# bms_2.net
KiCad netlist of a schematic drawn in EAGLE
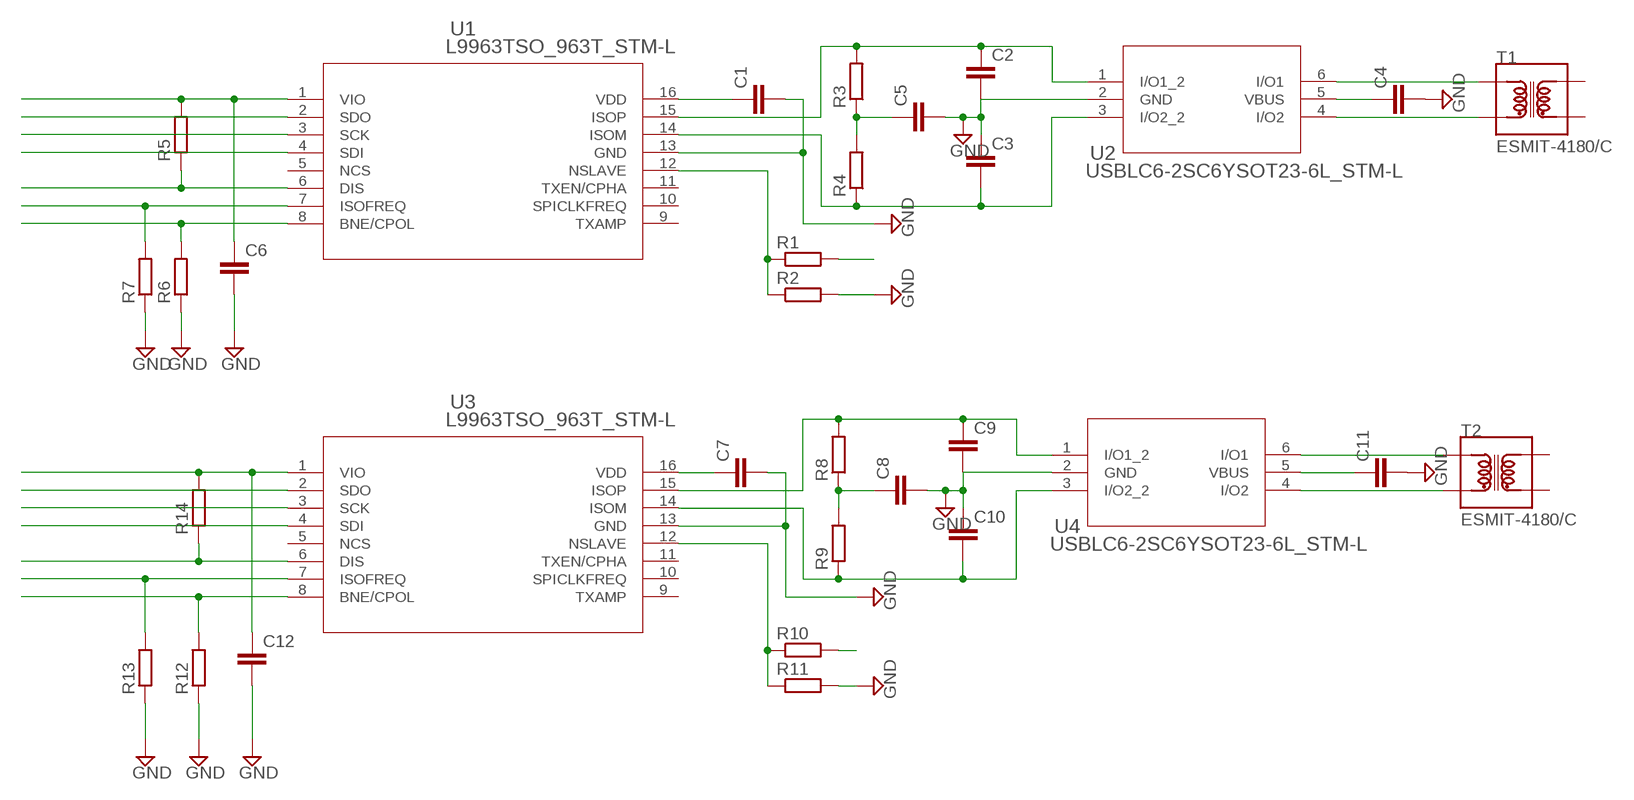
[diagram p0: schematic, sheet 1]

(export (version "E")
  (design (tool "Eeschema 10.0.6"))
  (components
    (comp (ref "C1")
      (value "C-EUC0402")
      (footprint "eagle-import:C0402")
      (libsource (lib "eagle-import") (part "C-EUC0402"))
    )
    (comp (ref "C2")
      (value "C-EUC0402")
      (footprint "eagle-import:C0402")
      (libsource (lib "eagle-import") (part "C-EUC0402"))
    )
    (comp (ref "C3")
      (value "C-EUC0402")
      (footprint "eagle-import:C0402")
      (libsource (lib "eagle-import") (part "C-EUC0402"))
    )
    (comp (ref "C4")
      (value "C-EUC0402")
      (footprint "eagle-import:C0402")
      (libsource (lib "eagle-import") (part "C-EUC0402"))
    )
    (comp (ref "C5")
      (value "C-EUC0402")
      (footprint "eagle-import:C0402")
      (libsource (lib "eagle-import") (part "C-EUC0402"))
    )
    (comp (ref "C6")
      (value "C-EUC0402")
      (footprint "eagle-import:C0402")
      (libsource (lib "eagle-import") (part "C-EUC0402"))
    )
    (comp (ref "C7")
      (value "C-EUC0402")
      (footprint "eagle-import:C0402")
      (libsource (lib "eagle-import") (part "C-EUC0402"))
    )
    (comp (ref "C8")
      (value "C-EUC0402")
      (footprint "eagle-import:C0402")
      (libsource (lib "eagle-import") (part "C-EUC0402"))
    )
    (comp (ref "C9")
      (value "C-EUC0402")
      (footprint "eagle-import:C0402")
      (libsource (lib "eagle-import") (part "C-EUC0402"))
    )
    (comp (ref "C10")
      (value "C-EUC0402")
      (footprint "eagle-import:C0402")
      (libsource (lib "eagle-import") (part "C-EUC0402"))
    )
    (comp (ref "C11")
      (value "C-EUC0402")
      (footprint "eagle-import:C0402")
      (libsource (lib "eagle-import") (part "C-EUC0402"))
    )
    (comp (ref "C12")
      (value "C-EUC0402")
      (footprint "eagle-import:C0402")
      (libsource (lib "eagle-import") (part "C-EUC0402"))
    )
    (comp (ref "R1")
      (value "R-EU_M0805")
      (footprint "eagle-import:M0805")
      (libsource (lib "eagle-import") (part "R-EU_M0805"))
    )
    (comp (ref "R2")
      (value "R-EU_M0805")
      (footprint "eagle-import:M0805")
      (libsource (lib "eagle-import") (part "R-EU_M0805"))
    )
    (comp (ref "R3")
      (value "R-EU_M0805")
      (footprint "eagle-import:M0805")
      (libsource (lib "eagle-import") (part "R-EU_M0805"))
    )
    (comp (ref "R4")
      (value "R-EU_M0805")
      (footprint "eagle-import:M0805")
      (libsource (lib "eagle-import") (part "R-EU_M0805"))
    )
    (comp (ref "R5")
      (value "R-EU_M0805")
      (footprint "eagle-import:M0805")
      (libsource (lib "eagle-import") (part "R-EU_M0805"))
    )
    (comp (ref "R6")
      (value "R-EU_M0805")
      (footprint "eagle-import:M0805")
      (libsource (lib "eagle-import") (part "R-EU_M0805"))
    )
    (comp (ref "R7")
      (value "R-EU_M0805")
      (footprint "eagle-import:M0805")
      (libsource (lib "eagle-import") (part "R-EU_M0805"))
    )
    (comp (ref "R8")
      (value "R-EU_M0805")
      (footprint "eagle-import:M0805")
      (libsource (lib "eagle-import") (part "R-EU_M0805"))
    )
    (comp (ref "R9")
      (value "R-EU_M0805")
      (footprint "eagle-import:M0805")
      (libsource (lib "eagle-import") (part "R-EU_M0805"))
    )
    (comp (ref "R10")
      (value "R-EU_M0805")
      (footprint "eagle-import:M0805")
      (libsource (lib "eagle-import") (part "R-EU_M0805"))
    )
    (comp (ref "R11")
      (value "R-EU_M0805")
      (footprint "eagle-import:M0805")
      (libsource (lib "eagle-import") (part "R-EU_M0805"))
    )
    (comp (ref "R12")
      (value "R-EU_M0805")
      (footprint "eagle-import:M0805")
      (libsource (lib "eagle-import") (part "R-EU_M0805"))
    )
    (comp (ref "R13")
      (value "R-EU_M0805")
      (footprint "eagle-import:M0805")
      (libsource (lib "eagle-import") (part "R-EU_M0805"))
    )
    (comp (ref "R14")
      (value "R-EU_M0805")
      (footprint "eagle-import:M0805")
      (libsource (lib "eagle-import") (part "R-EU_M0805"))
    )
    (comp (ref "T1")
      (value "ESMIT-4180/C")
      (footprint "eagle-import:XFMR_ESMIT-4180_C")
      (fields (field (name "MF") "Sumida America"))
      (libsource (lib "eagle-import") (part "ESMIT-4180/C"))
    )
    (comp (ref "T2")
      (value "ESMIT-4180/C")
      (footprint "eagle-import:XFMR_ESMIT-4180_C")
      (fields (field (name "MF") "Sumida America"))
      (libsource (lib "eagle-import") (part "ESMIT-4180/C"))
    )
    (comp (ref "U1")
      (value "L9963TSO_963T_STM-L")
      (footprint "eagle-import:SO_963T_STM-L")
      (fields
        (field (name "MANUFACTURER_PART_NUMBER") "L9963T")
        (field (name "COPYRIGHT") "Copyright (C) 2021 Ultra Librarian. All rights reserved.")
      )
      (libsource (lib "eagle-import") (part "L9963TSO_963T_STM-L"))
    )
    (comp (ref "U2")
      (value "USBLC6-2SC6YSOT23-6L_STM-L")
      (footprint "eagle-import:SOT23-6L_STM-L")
      (fields
        (field (name "MANUFACTURER_PART_NUMBER") "USBLC6-2SC6Y")
        (field (name "COPYRIGHT") "Copyright (C) 2021 Ultra Librarian. All rights reserved.")
      )
      (libsource (lib "eagle-import") (part "USBLC6-2SC6YSOT23-6L_STM-L"))
    )
    (comp (ref "U3")
      (value "L9963TSO_963T_STM-L")
      (footprint "eagle-import:SO_963T_STM-L")
      (fields
        (field (name "MANUFACTURER_PART_NUMBER") "L9963T")
        (field (name "COPYRIGHT") "Copyright (C) 2021 Ultra Librarian. All rights reserved.")
      )
      (libsource (lib "eagle-import") (part "L9963TSO_963T_STM-L"))
    )
    (comp (ref "U4")
      (value "USBLC6-2SC6YSOT23-6L_STM-L")
      (footprint "eagle-import:SOT23-6L_STM-L")
      (fields
        (field (name "MANUFACTURER_PART_NUMBER") "USBLC6-2SC6Y")
        (field (name "COPYRIGHT") "Copyright (C) 2021 Ultra Librarian. All rights reserved.")
      )
      (libsource (lib "eagle-import") (part "USBLC6-2SC6YSOT23-6L_STM-L"))
    )
  )
  (nets
    (net (code "1") (name "GND") (class "Default")
      (node (ref "C1") (pin "2") (pinfunction "2_2") (pintype "passive"))
      (node (ref "C10") (pin "1") (pinfunction "1_1") (pintype "passive"))
      (node (ref "C11") (pin "2") (pinfunction "2_2") (pintype "passive"))
      (node (ref "C12") (pin "2") (pinfunction "2_2") (pintype "passive"))
      (node (ref "C2") (pin "2") (pinfunction "2_2") (pintype "passive"))
      (node (ref "C3") (pin "1") (pinfunction "1_1") (pintype "passive"))
      (node (ref "C4") (pin "2") (pinfunction "2_2") (pintype "passive"))
      (node (ref "C5") (pin "2") (pinfunction "2_2") (pintype "passive"))
      (node (ref "C6") (pin "2") (pinfunction "2_2") (pintype "passive"))
      (node (ref "C7") (pin "2") (pinfunction "2_2") (pintype "passive"))
      (node (ref "C8") (pin "2") (pinfunction "2_2") (pintype "passive"))
      (node (ref "C9") (pin "2") (pinfunction "2_2") (pintype "passive"))
      (node (ref "R11") (pin "2") (pinfunction "2_2") (pintype "passive"))
      (node (ref "R12") (pin "1") (pinfunction "1_1") (pintype "passive"))
      (node (ref "R13") (pin "1") (pinfunction "1_1") (pintype "passive"))
      (node (ref "R2") (pin "2") (pinfunction "2_2") (pintype "passive"))
      (node (ref "R6") (pin "1") (pinfunction "1_1") (pintype "passive"))
      (node (ref "R7") (pin "1") (pinfunction "1_1") (pintype "passive"))
      (node (ref "U1") (pin "13") (pinfunction "GND_13") (pintype "passive"))
      (node (ref "U2") (pin "2") (pinfunction "GND_2") (pintype "power_in"))
      (node (ref "U3") (pin "13") (pinfunction "GND_13") (pintype "passive"))
      (node (ref "U4") (pin "2") (pinfunction "GND_2") (pintype "power_in"))
    )
    (net (code "2") (name "Net-(C5-Pad1)") (class "Default")
      (node (ref "C5") (pin "1") (pinfunction "1_1") (pintype "passive"))
      (node (ref "R3") (pin "1") (pinfunction "1_1") (pintype "passive"))
      (node (ref "R4") (pin "2") (pinfunction "2_2") (pintype "passive"))
    )
    (net (code "3") (name "Net-(C8-Pad1)") (class "Default")
      (node (ref "C8") (pin "1") (pinfunction "1_1") (pintype "passive"))
      (node (ref "R8") (pin "1") (pinfunction "1_1") (pintype "passive"))
      (node (ref "R9") (pin "2") (pinfunction "2_2") (pintype "passive"))
    )
    (net (code "4") (name "Net-(U1-BNE{slash}CPOL)") (class "Default")
      (node (ref "R6") (pin "2") (pinfunction "2_2") (pintype "passive"))
      (node (ref "U1") (pin "8") (pinfunction "BNE/CPOL_8") (pintype "passive"))
    )
    (net (code "5") (name "Net-(U1-DIS)") (class "Default")
      (node (ref "R5") (pin "1") (pinfunction "1_1") (pintype "passive"))
      (node (ref "U1") (pin "6") (pinfunction "DIS_6") (pintype "passive"))
    )
    (net (code "6") (name "Net-(U1-ISOFREQ)") (class "Default")
      (node (ref "R7") (pin "2") (pinfunction "2_2") (pintype "passive"))
      (node (ref "U1") (pin "7") (pinfunction "ISOFREQ_7") (pintype "passive"))
    )
    (net (code "7") (name "Net-(U1-ISOM)") (class "Default")
      (node (ref "C3") (pin "2") (pinfunction "2_2") (pintype "passive"))
      (node (ref "R4") (pin "1") (pinfunction "1_1") (pintype "passive"))
      (node (ref "U1") (pin "14") (pinfunction "ISOM_14") (pintype "passive"))
      (node (ref "U2") (pin "3") (pinfunction "I/O2_2_3") (pintype "bidirectional"))
    )
    (net (code "8") (name "Net-(U1-ISOP)") (class "Default")
      (node (ref "C2") (pin "1") (pinfunction "1_1") (pintype "passive"))
      (node (ref "R3") (pin "2") (pinfunction "2_2") (pintype "passive"))
      (node (ref "U1") (pin "15") (pinfunction "ISOP_15") (pintype "passive"))
      (node (ref "U2") (pin "1") (pinfunction "I/O1_2_1") (pintype "bidirectional"))
    )
    (net (code "9") (name "Net-(U1-NSLAVE)") (class "Default")
      (node (ref "R1") (pin "1") (pinfunction "1_1") (pintype "passive"))
      (node (ref "R2") (pin "1") (pinfunction "1_1") (pintype "passive"))
      (node (ref "U1") (pin "12") (pinfunction "NSLAVE_12") (pintype "passive"))
    )
    (net (code "10") (name "Net-(U1-VDD)") (class "Default")
      (node (ref "C1") (pin "1") (pinfunction "1_1") (pintype "passive"))
      (node (ref "U1") (pin "16") (pinfunction "VDD_16") (pintype "power_in"))
    )
    (net (code "11") (name "Net-(U1-VIO)") (class "Default")
      (node (ref "C6") (pin "1") (pinfunction "1_1") (pintype "passive"))
      (node (ref "R5") (pin "2") (pinfunction "2_2") (pintype "passive"))
      (node (ref "U1") (pin "1") (pinfunction "VIO_1") (pintype "passive"))
    )
    (net (code "12") (name "Net-(U2-I{slash}O1)") (class "Default")
      (node (ref "T1") (pin "2") (pinfunction "2_2") (pintype "passive"))
      (node (ref "U2") (pin "6") (pinfunction "I/O1_6") (pintype "bidirectional"))
    )
    (net (code "13") (name "Net-(U2-I{slash}O2)") (class "Default")
      (node (ref "T1") (pin "1") (pinfunction "1_1") (pintype "passive"))
      (node (ref "U2") (pin "4") (pinfunction "I/O2_4") (pintype "bidirectional"))
    )
    (net (code "14") (name "Net-(U2-VBUS)") (class "Default")
      (node (ref "C4") (pin "1") (pinfunction "1_1") (pintype "passive"))
      (node (ref "U2") (pin "5") (pinfunction "VBUS_5") (pintype "power_in"))
    )
    (net (code "15") (name "Net-(U3-BNE{slash}CPOL)") (class "Default")
      (node (ref "R12") (pin "2") (pinfunction "2_2") (pintype "passive"))
      (node (ref "U3") (pin "8") (pinfunction "BNE/CPOL_8") (pintype "passive"))
    )
    (net (code "16") (name "Net-(U3-DIS)") (class "Default")
      (node (ref "R14") (pin "1") (pinfunction "1_1") (pintype "passive"))
      (node (ref "U3") (pin "6") (pinfunction "DIS_6") (pintype "passive"))
    )
    (net (code "17") (name "Net-(U3-ISOFREQ)") (class "Default")
      (node (ref "R13") (pin "2") (pinfunction "2_2") (pintype "passive"))
      (node (ref "U3") (pin "7") (pinfunction "ISOFREQ_7") (pintype "passive"))
    )
    (net (code "18") (name "Net-(U3-ISOM)") (class "Default")
      (node (ref "C10") (pin "2") (pinfunction "2_2") (pintype "passive"))
      (node (ref "R9") (pin "1") (pinfunction "1_1") (pintype "passive"))
      (node (ref "U3") (pin "14") (pinfunction "ISOM_14") (pintype "passive"))
      (node (ref "U4") (pin "3") (pinfunction "I/O2_2_3") (pintype "bidirectional"))
    )
    (net (code "19") (name "Net-(U3-ISOP)") (class "Default")
      (node (ref "C9") (pin "1") (pinfunction "1_1") (pintype "passive"))
      (node (ref "R8") (pin "2") (pinfunction "2_2") (pintype "passive"))
      (node (ref "U3") (pin "15") (pinfunction "ISOP_15") (pintype "passive"))
      (node (ref "U4") (pin "1") (pinfunction "I/O1_2_1") (pintype "bidirectional"))
    )
    (net (code "20") (name "Net-(U3-NSLAVE)") (class "Default")
      (node (ref "R10") (pin "1") (pinfunction "1_1") (pintype "passive"))
      (node (ref "R11") (pin "1") (pinfunction "1_1") (pintype "passive"))
      (node (ref "U3") (pin "12") (pinfunction "NSLAVE_12") (pintype "passive"))
    )
    (net (code "21") (name "Net-(U3-VDD)") (class "Default")
      (node (ref "C7") (pin "1") (pinfunction "1_1") (pintype "passive"))
      (node (ref "U3") (pin "16") (pinfunction "VDD_16") (pintype "power_in"))
    )
    (net (code "22") (name "Net-(U3-VIO)") (class "Default")
      (node (ref "C12") (pin "1") (pinfunction "1_1") (pintype "passive"))
      (node (ref "R14") (pin "2") (pinfunction "2_2") (pintype "passive"))
      (node (ref "U3") (pin "1") (pinfunction "VIO_1") (pintype "passive"))
    )
    (net (code "23") (name "Net-(U4-I{slash}O1)") (class "Default")
      (node (ref "T2") (pin "2") (pinfunction "2_2") (pintype "passive"))
      (node (ref "U4") (pin "6") (pinfunction "I/O1_6") (pintype "bidirectional"))
    )
    (net (code "24") (name "Net-(U4-I{slash}O2)") (class "Default")
      (node (ref "T2") (pin "1") (pinfunction "1_1") (pintype "passive"))
      (node (ref "U4") (pin "4") (pinfunction "I/O2_4") (pintype "bidirectional"))
    )
    (net (code "25") (name "Net-(U4-VBUS)") (class "Default")
      (node (ref "C11") (pin "1") (pinfunction "1_1") (pintype "passive"))
      (node (ref "U4") (pin "5") (pinfunction "VBUS_5") (pintype "power_in"))
    )
    (net (code "26") (name "unconnected-(R1-Pad2)") (class "Default")
      (node (ref "R1") (pin "2") (pinfunction "2_2") (pintype "passive"))
    )
    (net (code "27") (name "unconnected-(R10-Pad2)") (class "Default")
      (node (ref "R10") (pin "2") (pinfunction "2_2") (pintype "passive"))
    )
    (net (code "28") (name "unconnected-(T1-Pad3)") (class "Default")
      (node (ref "T1") (pin "3") (pinfunction "3_3") (pintype "passive"))
    )
    (net (code "29") (name "unconnected-(T1-Pad4)") (class "Default")
      (node (ref "T1") (pin "4") (pinfunction "4_4") (pintype "passive"))
    )
    (net (code "30") (name "unconnected-(T2-Pad3)") (class "Default")
      (node (ref "T2") (pin "3") (pinfunction "3_3") (pintype "passive"))
    )
    (net (code "31") (name "unconnected-(T2-Pad4)") (class "Default")
      (node (ref "T2") (pin "4") (pinfunction "4_4") (pintype "passive"))
    )
    (net (code "32") (name "unconnected-(U1-NCS-Pad5)") (class "Default")
      (node (ref "U1") (pin "5") (pinfunction "NCS_5") (pintype "no_connect"))
    )
    (net (code "33") (name "unconnected-(U1-SCK-Pad3)") (class "Default")
      (node (ref "U1") (pin "3") (pinfunction "SCK_3") (pintype "passive"))
    )
    (net (code "34") (name "unconnected-(U1-SDI-Pad4)") (class "Default")
      (node (ref "U1") (pin "4") (pinfunction "SDI_4") (pintype "passive"))
    )
    (net (code "35") (name "unconnected-(U1-SDO-Pad2)") (class "Default")
      (node (ref "U1") (pin "2") (pinfunction "SDO_2") (pintype "passive"))
    )
    (net (code "36") (name "unconnected-(U1-SPICLKFREQ-Pad10)") (class "Default")
      (node (ref "U1") (pin "10") (pinfunction "SPICLKFREQ_10") (pintype "passive"))
    )
    (net (code "37") (name "unconnected-(U1-TXAMP-Pad9)") (class "Default")
      (node (ref "U1") (pin "9") (pinfunction "TXAMP_9") (pintype "passive"))
    )
    (net (code "38") (name "unconnected-(U1-TXEN{slash}CPHA-Pad11)") (class "Default")
      (node (ref "U1") (pin "11") (pinfunction "TXEN/CPHA_11") (pintype "passive"))
    )
    (net (code "39") (name "unconnected-(U3-NCS-Pad5)") (class "Default")
      (node (ref "U3") (pin "5") (pinfunction "NCS_5") (pintype "no_connect"))
    )
    (net (code "40") (name "unconnected-(U3-SCK-Pad3)") (class "Default")
      (node (ref "U3") (pin "3") (pinfunction "SCK_3") (pintype "passive"))
    )
    (net (code "41") (name "unconnected-(U3-SDI-Pad4)") (class "Default")
      (node (ref "U3") (pin "4") (pinfunction "SDI_4") (pintype "passive"))
    )
    (net (code "42") (name "unconnected-(U3-SDO-Pad2)") (class "Default")
      (node (ref "U3") (pin "2") (pinfunction "SDO_2") (pintype "passive"))
    )
    (net (code "43") (name "unconnected-(U3-SPICLKFREQ-Pad10)") (class "Default")
      (node (ref "U3") (pin "10") (pinfunction "SPICLKFREQ_10") (pintype "passive"))
    )
    (net (code "44") (name "unconnected-(U3-TXAMP-Pad9)") (class "Default")
      (node (ref "U3") (pin "9") (pinfunction "TXAMP_9") (pintype "passive"))
    )
    (net (code "45") (name "unconnected-(U3-TXEN{slash}CPHA-Pad11)") (class "Default")
      (node (ref "U3") (pin "11") (pinfunction "TXEN/CPHA_11") (pintype "passive"))
    )
  )
)
